# VFD-Power.net
KiCad netlist of a schematic drawn in EAGLE
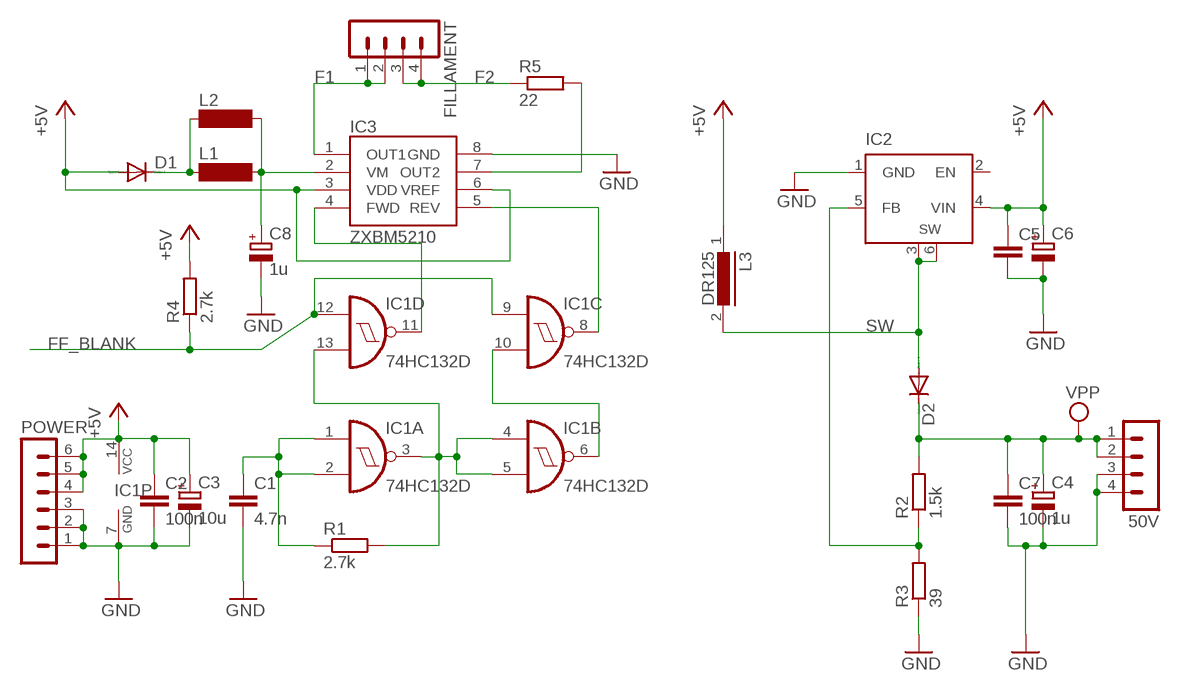
[diagram p0: schematic, sheet 1]

(export (version "E")
  (design (tool "Eeschema 10.0.6"))
  (components
    (comp (ref "50V")
      (value "MA04-1")
      (footprint "eagle-import:MA04-1")
      (libsource (lib "eagle-import") (part "MA04-1"))
    )
    (comp (ref "C1")
      (value "4.7n")
      (footprint "eagle-import:C1206")
      (libsource (lib "eagle-import") (part "C-EUC1206"))
    )
    (comp (ref "C2")
      (value "100n")
      (footprint "eagle-import:C1206")
      (libsource (lib "eagle-import") (part "C-EUC1206"))
    )
    (comp (ref "C3")
      (value "10u")
      (footprint "eagle-import:153CLV-0807")
      (libsource (lib "eagle-import") (part "CPOL-EU153CLV-0807"))
    )
    (comp (ref "C4")
      (value "1u")
      (footprint "eagle-import:153CLV-0505")
      (libsource (lib "eagle-import") (part "CPOL-EU153CLV-0505"))
    )
    (comp (ref "C5")
      (value "C-EUC1206")
      (footprint "eagle-import:C1206")
      (libsource (lib "eagle-import") (part "C-EUC1206"))
    )
    (comp (ref "C6")
      (value "CPOL-EU153CLV-0807")
      (footprint "eagle-import:153CLV-0807")
      (libsource (lib "eagle-import") (part "CPOL-EU153CLV-0807"))
    )
    (comp (ref "C7")
      (value "100n")
      (footprint "eagle-import:C1206")
      (libsource (lib "eagle-import") (part "C-EUC1206"))
    )
    (comp (ref "C8")
      (value "1u")
      (footprint "eagle-import:153CLV-0505")
      (libsource (lib "eagle-import") (part "CPOL-EU153CLV-0505"))
    )
    (comp (ref "D1")
      (value "DIODE-SMB")
      (footprint "eagle-import:SMB")
      (libsource (lib "eagle-import") (part "DIODE-SMB"))
    )
    (comp (ref "D2")
      (value "DIODE-SMB")
      (footprint "eagle-import:SMB")
      (libsource (lib "eagle-import") (part "DIODE-SMB"))
    )
    (comp (ref "FILLAMENT")
      (value "MA04-1")
      (footprint "eagle-import:MA04-1")
      (libsource (lib "eagle-import") (part "MA04-1"))
    )
    (comp (ref "IC1")
      (value "74HC132D")
      (footprint "eagle-import:SO14")
      (libsource (lib "eagle-import") (part "74132DHC"))
    )
    (comp (ref "IC2")
      (value "XL6009")
      (footprint "eagle-import:TO263-5")
      (libsource (lib "eagle-import") (part "XL6009"))
    )
    (comp (ref "IC3")
      (value "ZXBM5210")
      (footprint "eagle-import:SO8")
      (libsource (lib "eagle-import") (part "ZXBM5210"))
    )
    (comp (ref "L1")
      (value "SM-NE45")
      (footprint "eagle-import:SM-NE45")
      (libsource (lib "eagle-import") (part "SM-NE45"))
    )
    (comp (ref "L2")
      (value "MS85")
      (footprint "eagle-import:MS85")
      (libsource (lib "eagle-import") (part "MS85"))
    )
    (comp (ref "L3")
      (value "DR125")
      (footprint "eagle-import:DR125")
      (libsource (lib "eagle-import") (part "DR125"))
    )
    (comp (ref "POWER")
      (value "MA06-1")
      (footprint "eagle-import:MA06-1")
      (libsource (lib "eagle-import") (part "MA06-1"))
    )
    (comp (ref "R1")
      (value "2.7k")
      (footprint "eagle-import:R1206")
      (libsource (lib "eagle-import") (part "R-EU_R1206"))
    )
    (comp (ref "R2")
      (value "1.5k")
      (footprint "eagle-import:R1206")
      (libsource (lib "eagle-import") (part "R-EU_R1206"))
    )
    (comp (ref "R3")
      (value "39")
      (footprint "eagle-import:R1206")
      (libsource (lib "eagle-import") (part "R-EU_R1206"))
    )
    (comp (ref "R4")
      (value "2.7k")
      (footprint "eagle-import:R1206")
      (libsource (lib "eagle-import") (part "R-EU_R1206"))
    )
    (comp (ref "R5")
      (value "22")
      (footprint "eagle-import:0411_15")
      (libsource (lib "eagle-import") (part "R-EU_0411/15"))
    )
  )
  (nets
    (net (code "1") (name "+5V") (class "Default")
      (node (ref "C2") (pin "1") (pinfunction "1_1") (pintype "passive"))
      (node (ref "C3") (pin "+") (pinfunction "+_+") (pintype "passive"))
      (node (ref "C5") (pin "1") (pinfunction "1_1") (pintype "passive"))
      (node (ref "C6") (pin "+") (pinfunction "+_+") (pintype "passive"))
      (node (ref "D1") (pin "A") (pinfunction "A_A") (pintype "passive"))
      (node (ref "IC1") (pin "14") (pinfunction "VCC_14") (pintype "power_in"))
      (node (ref "IC2") (pin "4") (pinfunction "VIN_4") (pintype "input"))
      (node (ref "IC3") (pin "3") (pinfunction "VDD_3") (pintype "bidirectional"))
      (node (ref "IC3") (pin "6") (pinfunction "VREF_6") (pintype "bidirectional"))
      (node (ref "L3") (pin "1") (pinfunction "1_1") (pintype "passive"))
      (node (ref "POWER") (pin "4") (pinfunction "4_4") (pintype "passive"))
      (node (ref "POWER") (pin "5") (pinfunction "5_5") (pintype "passive"))
      (node (ref "POWER") (pin "6") (pinfunction "6_6") (pintype "passive"))
      (node (ref "R4") (pin "2") (pinfunction "2_2") (pintype "passive"))
    )
    (net (code "2") (name "/F1") (class "Default")
      (node (ref "FILLAMENT") (pin "1") (pinfunction "1_1") (pintype "passive"))
      (node (ref "FILLAMENT") (pin "2") (pinfunction "2_2") (pintype "passive"))
      (node (ref "IC3") (pin "1") (pinfunction "OUT1_1") (pintype "bidirectional"))
    )
    (net (code "3") (name "/F2") (class "Default")
      (node (ref "FILLAMENT") (pin "3") (pinfunction "3_3") (pintype "passive"))
      (node (ref "FILLAMENT") (pin "4") (pinfunction "4_4") (pintype "passive"))
      (node (ref "R5") (pin "1") (pinfunction "1_1") (pintype "passive"))
    )
    (net (code "4") (name "/FF_BLANK") (class "Default")
      (node (ref "IC1") (pin "12") (pinfunction "I0_12") (pintype "input"))
      (node (ref "IC1") (pin "9") (pinfunction "I0_9") (pintype "input"))
      (node (ref "R4") (pin "1") (pinfunction "1_1") (pintype "passive"))
    )
    (net (code "5") (name "/SW") (class "Default")
      (node (ref "D2") (pin "A") (pinfunction "A_A") (pintype "passive"))
      (node (ref "IC2") (pin "3") (pinfunction "SW_3") (pintype "power_in"))
      (node (ref "IC2") (pin "6") (pinfunction "SW_6") (pintype "power_in"))
      (node (ref "L3") (pin "2") (pinfunction "2_2") (pintype "passive"))
    )
    (net (code "6") (name "GND") (class "Default")
      (node (ref "50V") (pin "3") (pinfunction "3_3") (pintype "passive"))
      (node (ref "50V") (pin "4") (pinfunction "4_4") (pintype "passive"))
      (node (ref "C1") (pin "2") (pinfunction "2_2") (pintype "passive"))
      (node (ref "C2") (pin "2") (pinfunction "2_2") (pintype "passive"))
      (node (ref "C3") (pin "-") (pinfunction "-_-") (pintype "passive"))
      (node (ref "C4") (pin "-") (pinfunction "-_-") (pintype "passive"))
      (node (ref "C5") (pin "2") (pinfunction "2_2") (pintype "passive"))
      (node (ref "C6") (pin "-") (pinfunction "-_-") (pintype "passive"))
      (node (ref "C7") (pin "2") (pinfunction "2_2") (pintype "passive"))
      (node (ref "C8") (pin "-") (pinfunction "-_-") (pintype "passive"))
      (node (ref "IC1") (pin "7") (pinfunction "GND_7") (pintype "power_in"))
      (node (ref "IC2") (pin "1") (pinfunction "GND_1") (pintype "input"))
      (node (ref "IC3") (pin "8") (pinfunction "GND_8") (pintype "bidirectional"))
      (node (ref "POWER") (pin "1") (pinfunction "1_1") (pintype "passive"))
      (node (ref "POWER") (pin "2") (pinfunction "2_2") (pintype "passive"))
      (node (ref "POWER") (pin "3") (pinfunction "3_3") (pintype "passive"))
      (node (ref "R3") (pin "1") (pinfunction "1_1") (pintype "passive"))
    )
    (net (code "7") (name "Net-(D1-PadC)") (class "Default")
      (node (ref "D1") (pin "C") (pinfunction "C_C") (pintype "passive"))
      (node (ref "L1") (pin "1") (pinfunction "1_1") (pintype "passive"))
      (node (ref "L2") (pin "1") (pinfunction "1_1") (pintype "passive"))
    )
    (net (code "8") (name "Net-(IC1A-I0)") (class "Default")
      (node (ref "C1") (pin "1") (pinfunction "1_1") (pintype "passive"))
      (node (ref "IC1") (pin "1") (pinfunction "I0_1") (pintype "input"))
      (node (ref "IC1") (pin "2") (pinfunction "I1_2") (pintype "input"))
      (node (ref "R1") (pin "1") (pinfunction "1_1") (pintype "passive"))
    )
    (net (code "9") (name "Net-(IC1A-O)") (class "Default")
      (node (ref "IC1") (pin "13") (pinfunction "I1_13") (pintype "input"))
      (node (ref "IC1") (pin "3") (pinfunction "O_3") (pintype "output"))
      (node (ref "IC1") (pin "4") (pinfunction "I0_4") (pintype "input"))
      (node (ref "IC1") (pin "5") (pinfunction "I1_5") (pintype "input"))
      (node (ref "R1") (pin "2") (pinfunction "2_2") (pintype "passive"))
    )
    (net (code "10") (name "Net-(IC1B-O)") (class "Default")
      (node (ref "IC1") (pin "10") (pinfunction "I1_10") (pintype "input"))
      (node (ref "IC1") (pin "6") (pinfunction "O_6") (pintype "output"))
    )
    (net (code "11") (name "Net-(IC1C-O)") (class "Default")
      (node (ref "IC1") (pin "8") (pinfunction "O_8") (pintype "output"))
      (node (ref "IC3") (pin "5") (pinfunction "REV_5") (pintype "bidirectional"))
    )
    (net (code "12") (name "Net-(IC1D-O)") (class "Default")
      (node (ref "IC1") (pin "11") (pinfunction "O_11") (pintype "output"))
      (node (ref "IC3") (pin "4") (pinfunction "FWD_4") (pintype "bidirectional"))
    )
    (net (code "13") (name "Net-(IC2-FB)") (class "Default")
      (node (ref "IC2") (pin "5") (pinfunction "FB_5") (pintype "input"))
      (node (ref "R2") (pin "1") (pinfunction "1_1") (pintype "passive"))
      (node (ref "R3") (pin "2") (pinfunction "2_2") (pintype "passive"))
    )
    (net (code "14") (name "Net-(IC3-OUT2)") (class "Default")
      (node (ref "IC3") (pin "7") (pinfunction "OUT2_7") (pintype "bidirectional"))
      (node (ref "R5") (pin "2") (pinfunction "2_2") (pintype "passive"))
    )
    (net (code "15") (name "Net-(IC3-VM)") (class "Default")
      (node (ref "C8") (pin "+") (pinfunction "+_+") (pintype "passive"))
      (node (ref "IC3") (pin "2") (pinfunction "VM_2") (pintype "bidirectional"))
      (node (ref "L1") (pin "2") (pinfunction "2_2") (pintype "passive"))
      (node (ref "L2") (pin "2") (pinfunction "2_2") (pintype "passive"))
    )
    (net (code "16") (name "VPP") (class "Default")
      (node (ref "50V") (pin "1") (pinfunction "1_1") (pintype "passive"))
      (node (ref "50V") (pin "2") (pinfunction "2_2") (pintype "passive"))
      (node (ref "C4") (pin "+") (pinfunction "+_+") (pintype "passive"))
      (node (ref "C7") (pin "1") (pinfunction "1_1") (pintype "passive"))
      (node (ref "D2") (pin "C") (pinfunction "C_C") (pintype "passive"))
      (node (ref "R2") (pin "2") (pinfunction "2_2") (pintype "passive"))
    )
    (net (code "17") (name "unconnected-(IC2-EN-Pad2)") (class "Default")
      (node (ref "IC2") (pin "2") (pinfunction "EN_2") (pintype "output"))
    )
  )
)
